# POGO_Tester_Rev1_Top_Level.net
KiCad netlist of a schematic drawn in Altium Designer
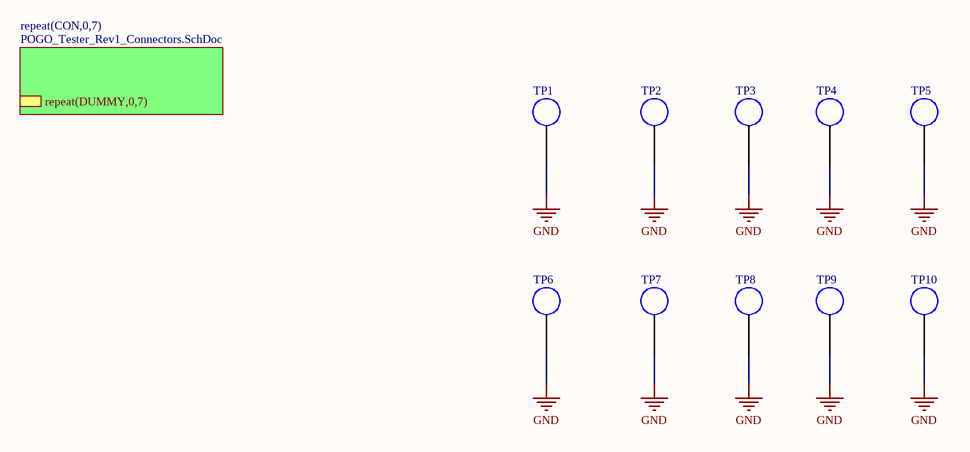
[diagram p0: POGO_Tester_Rev1_Top_Level.SchDoc]

(export (version "E")
  (design (tool "Eeschema 10.0.6"))
  (components
    (comp (ref "TP1")
      (value "DNI")
      (footprint "250milx400mil")
      (description "250milx400mil Square Pad")
      (libsource (lib "Avery Schem Library") (part "TEST POINT"))
    )
    (comp (ref "TP2")
      (value "DNI")
      (footprint "250milx400mil")
      (description "250milx400mil Square Pad")
      (libsource (lib "Avery Schem Library") (part "TEST POINT"))
    )
    (comp (ref "TP3")
      (value "DNI")
      (footprint "250milx400mil")
      (description "250milx400mil Square Pad")
      (libsource (lib "Avery Schem Library") (part "TEST POINT"))
    )
    (comp (ref "TP4")
      (value "DNI")
      (footprint "250milx400mil")
      (description "250milx400mil Square Pad")
      (libsource (lib "Avery Schem Library") (part "TEST POINT"))
    )
    (comp (ref "TP5")
      (value "DNI")
      (footprint "250milx400mil")
      (description "250milx400mil Square Pad")
      (libsource (lib "Avery Schem Library") (part "TEST POINT"))
    )
    (comp (ref "TP6")
      (value "DNI")
      (footprint "250milx400mil")
      (description "250milx400mil Square Pad")
      (libsource (lib "Avery Schem Library") (part "TEST POINT"))
    )
    (comp (ref "TP7")
      (value "DNI")
      (footprint "250milx400mil")
      (description "250milx400mil Square Pad")
      (libsource (lib "Avery Schem Library") (part "TEST POINT"))
    )
    (comp (ref "TP8")
      (value "DNI")
      (footprint "250milx400mil")
      (description "250milx400mil Square Pad")
      (libsource (lib "Avery Schem Library") (part "TEST POINT"))
    )
    (comp (ref "TP9")
      (value "DNI")
      (footprint "250milx400mil")
      (description "250milx400mil Square Pad")
      (libsource (lib "Avery Schem Library") (part "TEST POINT"))
    )
    (comp (ref "TP10")
      (value "DNI")
      (footprint "250milx400mil")
      (description "250milx400mil Square Pad")
      (libsource (lib "Avery Schem Library") (part "TEST POINT"))
    )
  )
  (nets
    (net (code "2") (name "GND") (class "Default")
      (node (ref "TP1") (pin "1") (pinfunction "1_1") (pintype "passive"))
      (node (ref "TP10") (pin "1") (pinfunction "1_1") (pintype "passive"))
      (node (ref "TP2") (pin "1") (pinfunction "1_1") (pintype "passive"))
      (node (ref "TP3") (pin "1") (pinfunction "1_1") (pintype "passive"))
      (node (ref "TP4") (pin "1") (pinfunction "1_1") (pintype "passive"))
      (node (ref "TP5") (pin "1") (pinfunction "1_1") (pintype "passive"))
      (node (ref "TP6") (pin "1") (pinfunction "1_1") (pintype "passive"))
      (node (ref "TP7") (pin "1") (pinfunction "1_1") (pintype "passive"))
      (node (ref "TP8") (pin "1") (pinfunction "1_1") (pintype "passive"))
      (node (ref "TP9") (pin "1") (pinfunction "1_1") (pintype "passive"))
    )
  )
)
